# powerSupply.net
KiCad netlist of a schematic drawn in EAGLE
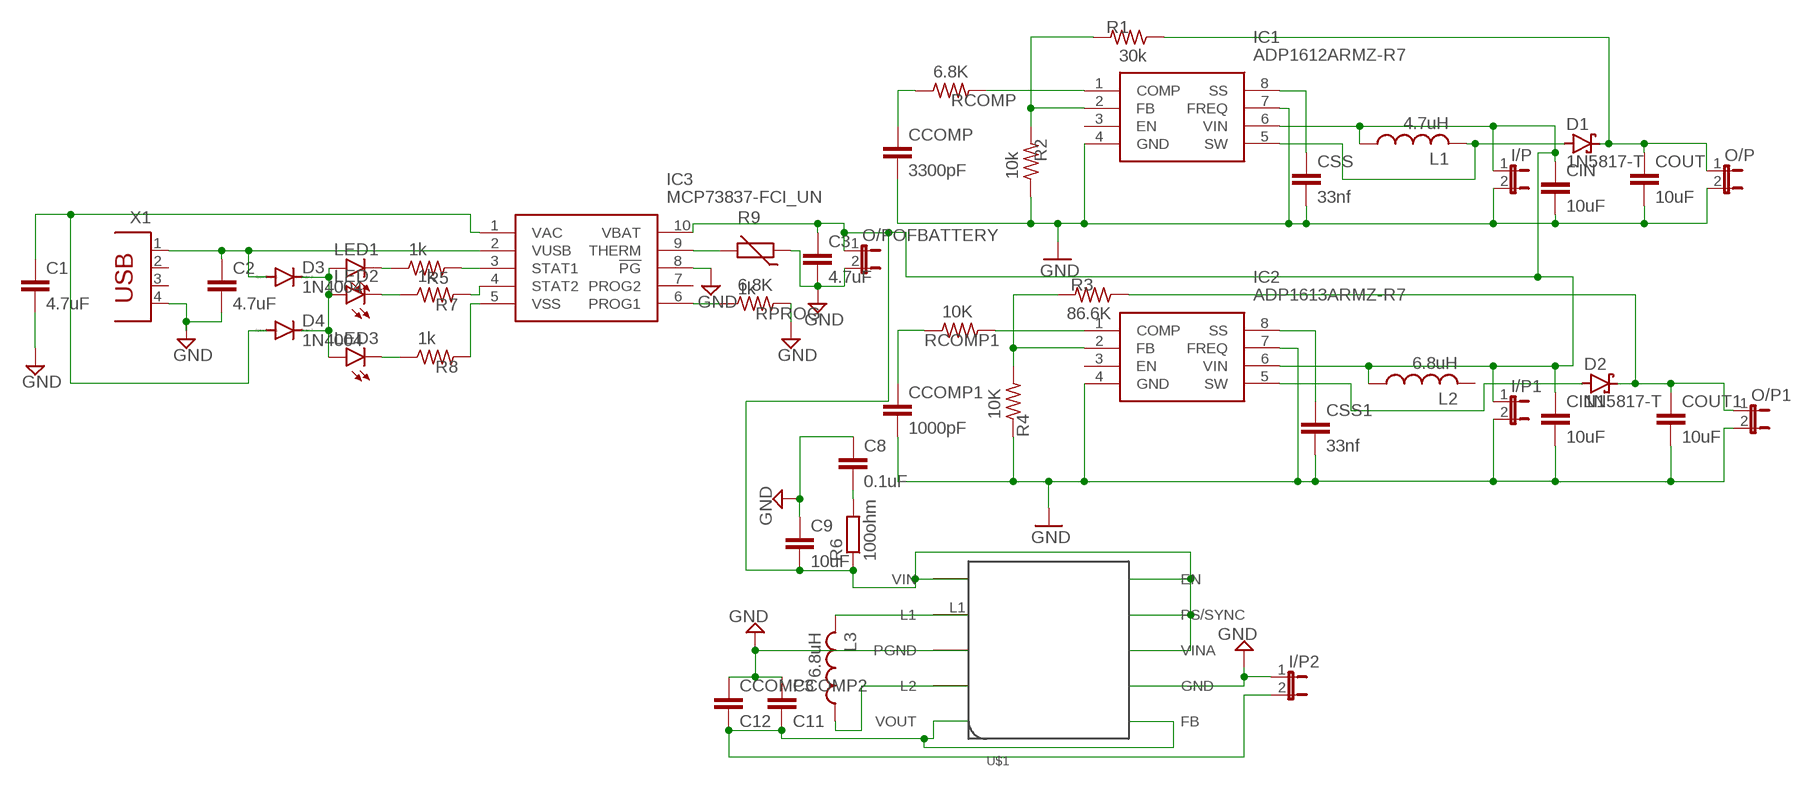
[diagram p0: schematic, sheet 1]

(export (version "E")
  (design (tool "Eeschema 10.0.6"))
  (components
    (comp (ref "C1")
      (value "4.7uF")
      (footprint "eagle-import:C025-024X044")
      (libsource (lib "eagle-import") (part "C-EU025-024X044"))
    )
    (comp (ref "C2")
      (value "4.7uF")
      (footprint "eagle-import:C025-024X044")
      (libsource (lib "eagle-import") (part "C-EU025-024X044"))
    )
    (comp (ref "C3")
      (value "4.7uF")
      (footprint "eagle-import:C025-024X044")
      (libsource (lib "eagle-import") (part "C-EU025-024X044"))
    )
    (comp (ref "C8")
      (value "0.1uF")
      (footprint "eagle-import:C025-024X044")
      (libsource (lib "eagle-import") (part "C-EU025-024X044"))
    )
    (comp (ref "C9")
      (value "10uF")
      (footprint "eagle-import:C025-024X044")
      (libsource (lib "eagle-import") (part "C-EU025-024X044"))
    )
    (comp (ref "CCOMP")
      (value "3300pF")
      (footprint "eagle-import:C025-024X044")
      (libsource (lib "eagle-import") (part "C-EU025-024X044"))
    )
    (comp (ref "CCOMP1")
      (value "1000pF")
      (footprint "eagle-import:C025-024X044")
      (libsource (lib "eagle-import") (part "C-EU025-024X044"))
    )
    (comp (ref "CCOMP2")
      (value "C11")
      (footprint "eagle-import:C025-024X044")
      (libsource (lib "eagle-import") (part "C-EU025-024X044"))
    )
    (comp (ref "CCOMP3")
      (value "C12")
      (footprint "eagle-import:C025-024X044")
      (libsource (lib "eagle-import") (part "C-EU025-024X044"))
    )
    (comp (ref "CIN")
      (value "10uF")
      (footprint "eagle-import:C025-024X044")
      (libsource (lib "eagle-import") (part "C-EU025-024X044"))
    )
    (comp (ref "CIN1")
      (value "10uF")
      (footprint "eagle-import:C025-024X044")
      (libsource (lib "eagle-import") (part "C-EU025-024X044"))
    )
    (comp (ref "COUT")
      (value "10uF")
      (footprint "eagle-import:C025-024X044")
      (libsource (lib "eagle-import") (part "C-EU025-024X044"))
    )
    (comp (ref "COUT1")
      (value "10uF")
      (footprint "eagle-import:C025-024X044")
      (libsource (lib "eagle-import") (part "C-EU025-024X044"))
    )
    (comp (ref "CSS")
      (value "33nf")
      (footprint "eagle-import:C025-024X044")
      (libsource (lib "eagle-import") (part "C-EU025-024X044"))
    )
    (comp (ref "CSS1")
      (value "33nf")
      (footprint "eagle-import:C025-024X044")
      (libsource (lib "eagle-import") (part "C-EU025-024X044"))
    )
    (comp (ref "D1")
      (value "1N5817-T")
      (footprint "eagle-import:SOD323_ST")
      (libsource (lib "eagle-import") (part "BAT60J"))
    )
    (comp (ref "D2")
      (value "1N5817-T")
      (footprint "eagle-import:SOD323_ST")
      (libsource (lib "eagle-import") (part "BAT60J"))
    )
    (comp (ref "D3")
      (value "1N4004")
      (footprint "eagle-import:DO41-10")
      (libsource (lib "eagle-import") (part "1N4004"))
    )
    (comp (ref "D4")
      (value "1N4004")
      (footprint "eagle-import:DO41-10")
      (libsource (lib "eagle-import") (part "1N4004"))
    )
    (comp (ref "I/P")
      (value "JP1E")
      (footprint "eagle-import:JP1")
      (libsource (lib "eagle-import") (part "JP1E"))
    )
    (comp (ref "I/P1")
      (value "JP1E")
      (footprint "eagle-import:JP1")
      (libsource (lib "eagle-import") (part "JP1E"))
    )
    (comp (ref "I/P2")
      (value "JP1E")
      (footprint "eagle-import:JP1")
      (libsource (lib "eagle-import") (part "JP1E"))
    )
    (comp (ref "IC1")
      (value "ADP1612ARMZ-R7")
      (footprint "eagle-import:SOP65P490X110-8N")
      (fields (field (name "MOUSER_PART_NUMBER") "584-ADP1612ARMZ-R7"))
      (libsource (lib "eagle-import") (part "ADP1612ARMZ-R7"))
    )
    (comp (ref "IC2")
      (value "ADP1613ARMZ-R7")
      (footprint "eagle-import:SOP65P490X110-8N")
      (fields (field (name "MOUSER_PART_NUMBER") "584-ADP1613ARMZ-R7"))
      (libsource (lib "eagle-import") (part "ADP1613ARMZ-R7"))
    )
    (comp (ref "IC3")
      (value "MCP73837-FCI_UN")
      (footprint "eagle-import:SOP50P490X110-10N")
      (fields
        (field (name "ARROW_PART_NUMBER") "MCP73837-FCI/UN")
        (field (name "MOUSER_PART_NUMBER") "579-MCP73837-FCI/UN")
      )
      (libsource (lib "eagle-import") (part "MCP73837-FCI_UN"))
    )
    (comp (ref "L1")
      (value "4.7uH")
      (footprint "eagle-import:0204_7")
      (libsource (lib "eagle-import") (part "L-US0204/7"))
    )
    (comp (ref "L2")
      (value "6.8uH")
      (footprint "eagle-import:0204_7")
      (libsource (lib "eagle-import") (part "L-US0204/7"))
    )
    (comp (ref "L3")
      (value "6.8uH")
      (footprint "eagle-import:0204_7")
      (libsource (lib "eagle-import") (part "L-US0204/7"))
    )
    (comp (ref "LED1")
      (value "LED5MM")
      (footprint "eagle-import:LED5MM")
      (libsource (lib "eagle-import") (part "LED5MM"))
    )
    (comp (ref "LED2")
      (value "LED5MM")
      (footprint "eagle-import:LED5MM")
      (libsource (lib "eagle-import") (part "LED5MM"))
    )
    (comp (ref "LED3")
      (value "LED5MM")
      (footprint "eagle-import:LED5MM")
      (libsource (lib "eagle-import") (part "LED5MM"))
    )
    (comp (ref "O/P")
      (value "JP1E")
      (footprint "eagle-import:JP1")
      (libsource (lib "eagle-import") (part "JP1E"))
    )
    (comp (ref "O/P1")
      (value "JP1E")
      (footprint "eagle-import:JP1")
      (libsource (lib "eagle-import") (part "JP1E"))
    )
    (comp (ref "O/POFBATTERY")
      (value "JP1E")
      (footprint "eagle-import:JP1")
      (libsource (lib "eagle-import") (part "JP1E"))
    )
    (comp (ref "R1")
      (value "30k")
      (footprint "eagle-import:0204V")
      (libsource (lib "eagle-import") (part "R-US_0204/2V"))
    )
    (comp (ref "R2")
      (value "10k")
      (footprint "eagle-import:0204V")
      (libsource (lib "eagle-import") (part "R-US_0204/2V"))
    )
    (comp (ref "R3")
      (value "86.6K")
      (footprint "eagle-import:0204V")
      (libsource (lib "eagle-import") (part "R-US_0204/2V"))
    )
    (comp (ref "R4")
      (value "10K")
      (footprint "eagle-import:0204V")
      (libsource (lib "eagle-import") (part "R-US_0204/2V"))
    )
    (comp (ref "R5")
      (value "1k")
      (footprint "eagle-import:0204V")
      (libsource (lib "eagle-import") (part "R-US_0204/2V"))
    )
    (comp (ref "R6")
      (value "100ohm")
      (footprint "eagle-import:0207_10")
      (libsource (lib "eagle-import") (part "R-EU_0207/10"))
    )
    (comp (ref "R7")
      (value "1k")
      (footprint "eagle-import:0204V")
      (libsource (lib "eagle-import") (part "R-US_0204/2V"))
    )
    (comp (ref "R8")
      (value "1k")
      (footprint "eagle-import:0204V")
      (libsource (lib "eagle-import") (part "R-US_0204/2V"))
    )
    (comp (ref "R9")
      (value "1k")
      (footprint "eagle-import:RS-2,5")
      (libsource (lib "eagle-import") (part "THERMISTOR-2,5"))
    )
    (comp (ref "RCOMP")
      (value "6.8K")
      (footprint "eagle-import:0204V")
      (libsource (lib "eagle-import") (part "R-US_0204/2V"))
    )
    (comp (ref "RCOMP1")
      (value "10K")
      (footprint "eagle-import:0204V")
      (libsource (lib "eagle-import") (part "R-US_0204/2V"))
    )
    (comp (ref "RPROG")
      (value "6.8K")
      (footprint "eagle-import:0204V")
      (libsource (lib "eagle-import") (part "R-US_0204/2V"))
    )
    (comp (ref "U$1")
      (value "TPS63002")
      (footprint "eagle-import:TPS63002")
      (libsource (lib "eagle-import") (part "TPS63002"))
    )
    (comp (ref "X1")
      (value "PN87520")
      (footprint "eagle-import:PN87520")
      (libsource (lib "eagle-import") (part "PN87520"))
    )
  )
  (nets
    (net (code "1") (name "GND") (class "Default")
      (node (ref "C1") (pin "2") (pinfunction "2_2") (pintype "passive"))
      (node (ref "C2") (pin "2") (pinfunction "2_2") (pintype "passive"))
      (node (ref "C3") (pin "2") (pinfunction "2_2") (pintype "passive"))
      (node (ref "C8") (pin "1") (pinfunction "1_1") (pintype "passive"))
      (node (ref "C9") (pin "1") (pinfunction "1_1") (pintype "passive"))
      (node (ref "CCOMP") (pin "2") (pinfunction "2_2") (pintype "passive"))
      (node (ref "CCOMP1") (pin "2") (pinfunction "2_2") (pintype "passive"))
      (node (ref "CCOMP2") (pin "1") (pinfunction "1_1") (pintype "passive"))
      (node (ref "CCOMP3") (pin "1") (pinfunction "1_1") (pintype "passive"))
      (node (ref "CIN") (pin "2") (pinfunction "2_2") (pintype "passive"))
      (node (ref "CIN1") (pin "2") (pinfunction "2_2") (pintype "passive"))
      (node (ref "COUT") (pin "2") (pinfunction "2_2") (pintype "passive"))
      (node (ref "COUT1") (pin "2") (pinfunction "2_2") (pintype "passive"))
      (node (ref "CSS") (pin "2") (pinfunction "2_2") (pintype "passive"))
      (node (ref "CSS1") (pin "2") (pinfunction "2_2") (pintype "passive"))
      (node (ref "I/P") (pin "2") (pinfunction "2_2") (pintype "passive"))
      (node (ref "I/P1") (pin "2") (pinfunction "2_2") (pintype "passive"))
      (node (ref "I/P2") (pin "1") (pinfunction "1_1") (pintype "passive"))
      (node (ref "IC1") (pin "4") (pinfunction "GND_4") (pintype "bidirectional"))
      (node (ref "IC1") (pin "7") (pinfunction "FREQ_7") (pintype "bidirectional"))
      (node (ref "IC2") (pin "4") (pinfunction "GND_4") (pintype "bidirectional"))
      (node (ref "IC2") (pin "7") (pinfunction "FREQ_7") (pintype "bidirectional"))
      (node (ref "IC3") (pin "8") (pinfunction "~{PG}_8") (pintype "bidirectional"))
      (node (ref "O/P") (pin "2") (pinfunction "2_2") (pintype "passive"))
      (node (ref "O/P1") (pin "2") (pinfunction "2_2") (pintype "passive"))
      (node (ref "O/POFBATTERY") (pin "2") (pinfunction "2_2") (pintype "passive"))
      (node (ref "R2") (pin "1") (pinfunction "1_1") (pintype "passive"))
      (node (ref "R4") (pin "1") (pinfunction "1_1") (pintype "passive"))
      (node (ref "R9") (pin "1") (pinfunction "1_1") (pintype "passive"))
      (node (ref "RPROG") (pin "2") (pinfunction "2_2") (pintype "passive"))
      (node (ref "U$1") (pin "GND") (pinfunction "GND_GND") (pintype "bidirectional"))
      (node (ref "U$1") (pin "PGND") (pinfunction "PGND_PGND") (pintype "bidirectional"))
      (node (ref "X1") (pin "4") (pinfunction "4_4") (pintype "passive"))
    )
    (net (code "2") (name "Net-(C8-Pad2)") (class "Default")
      (node (ref "C8") (pin "2") (pinfunction "2_2") (pintype "passive"))
      (node (ref "R6") (pin "2") (pinfunction "2_2") (pintype "passive"))
    )
    (net (code "3") (name "Net-(CCOMP-Pad1)") (class "Default")
      (node (ref "CCOMP") (pin "1") (pinfunction "1_1") (pintype "passive"))
      (node (ref "RCOMP") (pin "1") (pinfunction "1_1") (pintype "passive"))
    )
    (net (code "4") (name "Net-(CCOMP1-Pad1)") (class "Default")
      (node (ref "CCOMP1") (pin "1") (pinfunction "1_1") (pintype "passive"))
      (node (ref "RCOMP1") (pin "1") (pinfunction "1_1") (pintype "passive"))
    )
    (net (code "5") (name "Net-(CCOMP2-Pad2)") (class "Default")
      (node (ref "CCOMP2") (pin "2") (pinfunction "2_2") (pintype "passive"))
      (node (ref "CCOMP3") (pin "2") (pinfunction "2_2") (pintype "passive"))
      (node (ref "I/P2") (pin "2") (pinfunction "2_2") (pintype "passive"))
      (node (ref "U$1") (pin "FB") (pinfunction "FB_FB") (pintype "bidirectional"))
      (node (ref "U$1") (pin "VOUT") (pinfunction "VOUT_VOUT") (pintype "bidirectional"))
    )
    (net (code "6") (name "Net-(COUT-Pad1)") (class "Default")
      (node (ref "COUT") (pin "1") (pinfunction "1_1") (pintype "passive"))
      (node (ref "D1") (pin "C") (pinfunction "C_C") (pintype "passive"))
      (node (ref "O/P") (pin "1") (pinfunction "1_1") (pintype "passive"))
      (node (ref "R1") (pin "1") (pinfunction "1_1") (pintype "passive"))
    )
    (net (code "7") (name "Net-(COUT1-Pad1)") (class "Default")
      (node (ref "COUT1") (pin "1") (pinfunction "1_1") (pintype "passive"))
      (node (ref "D2") (pin "C") (pinfunction "C_C") (pintype "passive"))
      (node (ref "O/P1") (pin "1") (pinfunction "1_1") (pintype "passive"))
      (node (ref "R3") (pin "1") (pinfunction "1_1") (pintype "passive"))
    )
    (net (code "8") (name "Net-(D3-PadC)") (class "Default")
      (node (ref "D3") (pin "C") (pinfunction "C_C") (pintype "passive"))
      (node (ref "D4") (pin "C") (pinfunction "C_C") (pintype "passive"))
      (node (ref "LED1") (pin "A") (pinfunction "A_A") (pintype "passive"))
      (node (ref "LED2") (pin "A") (pinfunction "A_A") (pintype "passive"))
      (node (ref "LED3") (pin "A") (pinfunction "A_A") (pintype "passive"))
    )
    (net (code "9") (name "Net-(IC1-COMP)") (class "Default")
      (node (ref "IC1") (pin "1") (pinfunction "COMP_1") (pintype "bidirectional"))
      (node (ref "RCOMP") (pin "2") (pinfunction "2_2") (pintype "passive"))
    )
    (net (code "10") (name "Net-(IC1-FB)") (class "Default")
      (node (ref "IC1") (pin "2") (pinfunction "FB_2") (pintype "bidirectional"))
      (node (ref "R1") (pin "2") (pinfunction "2_2") (pintype "passive"))
      (node (ref "R2") (pin "2") (pinfunction "2_2") (pintype "passive"))
    )
    (net (code "11") (name "Net-(IC1-SS)") (class "Default")
      (node (ref "CSS") (pin "1") (pinfunction "1_1") (pintype "passive"))
      (node (ref "IC1") (pin "8") (pinfunction "SS_8") (pintype "bidirectional"))
    )
    (net (code "12") (name "Net-(IC1-SW)") (class "Default")
      (node (ref "D1") (pin "A") (pinfunction "A_A") (pintype "passive"))
      (node (ref "IC1") (pin "5") (pinfunction "SW_5") (pintype "bidirectional"))
      (node (ref "L1") (pin "2") (pinfunction "2_2") (pintype "passive"))
    )
    (net (code "13") (name "Net-(IC1-VIN)") (class "Default")
      (node (ref "C3") (pin "1") (pinfunction "1_1") (pintype "passive"))
      (node (ref "C9") (pin "2") (pinfunction "2_2") (pintype "passive"))
      (node (ref "CIN") (pin "1") (pinfunction "1_1") (pintype "passive"))
      (node (ref "CIN1") (pin "1") (pinfunction "1_1") (pintype "passive"))
      (node (ref "I/P") (pin "1") (pinfunction "1_1") (pintype "passive"))
      (node (ref "I/P1") (pin "1") (pinfunction "1_1") (pintype "passive"))
      (node (ref "IC1") (pin "6") (pinfunction "VIN_6") (pintype "bidirectional"))
      (node (ref "IC2") (pin "6") (pinfunction "VIN_6") (pintype "bidirectional"))
      (node (ref "IC3") (pin "10") (pinfunction "VBAT_10") (pintype "bidirectional"))
      (node (ref "L1") (pin "1") (pinfunction "1_1") (pintype "passive"))
      (node (ref "L2") (pin "1") (pinfunction "1_1") (pintype "passive"))
      (node (ref "O/POFBATTERY") (pin "1") (pinfunction "1_1") (pintype "passive"))
      (node (ref "R6") (pin "1") (pinfunction "1_1") (pintype "passive"))
      (node (ref "U$1") (pin "EN") (pinfunction "EN_EN") (pintype "bidirectional"))
      (node (ref "U$1") (pin "PS/SYNC") (pinfunction "PS/SYNC_PS/SYNC") (pintype "bidirectional"))
      (node (ref "U$1") (pin "VIN") (pinfunction "VIN_VIN") (pintype "bidirectional"))
      (node (ref "U$1") (pin "VINA") (pinfunction "VINA_VINA") (pintype "bidirectional"))
    )
    (net (code "14") (name "Net-(IC2-COMP)") (class "Default")
      (node (ref "IC2") (pin "1") (pinfunction "COMP_1") (pintype "bidirectional"))
      (node (ref "RCOMP1") (pin "2") (pinfunction "2_2") (pintype "passive"))
    )
    (net (code "15") (name "Net-(IC2-FB)") (class "Default")
      (node (ref "IC2") (pin "2") (pinfunction "FB_2") (pintype "bidirectional"))
      (node (ref "R3") (pin "2") (pinfunction "2_2") (pintype "passive"))
      (node (ref "R4") (pin "2") (pinfunction "2_2") (pintype "passive"))
    )
    (net (code "16") (name "Net-(IC2-SS)") (class "Default")
      (node (ref "CSS1") (pin "1") (pinfunction "1_1") (pintype "passive"))
      (node (ref "IC2") (pin "8") (pinfunction "SS_8") (pintype "bidirectional"))
    )
    (net (code "17") (name "Net-(IC2-SW)") (class "Default")
      (node (ref "D2") (pin "A") (pinfunction "A_A") (pintype "passive"))
      (node (ref "IC2") (pin "5") (pinfunction "SW_5") (pintype "bidirectional"))
    )
    (net (code "18") (name "Net-(IC3-PROG1)") (class "Default")
      (node (ref "IC3") (pin "6") (pinfunction "PROG1_6") (pintype "bidirectional"))
      (node (ref "RPROG") (pin "1") (pinfunction "1_1") (pintype "passive"))
    )
    (net (code "19") (name "Net-(IC3-STAT1)") (class "Default")
      (node (ref "IC3") (pin "3") (pinfunction "STAT1_3") (pintype "bidirectional"))
      (node (ref "R5") (pin "2") (pinfunction "2_2") (pintype "passive"))
    )
    (net (code "20") (name "Net-(IC3-STAT2)") (class "Default")
      (node (ref "IC3") (pin "4") (pinfunction "STAT2_4") (pintype "bidirectional"))
      (node (ref "R7") (pin "2") (pinfunction "2_2") (pintype "passive"))
    )
    (net (code "21") (name "Net-(IC3-THERM)") (class "Default")
      (node (ref "IC3") (pin "9") (pinfunction "THERM_9") (pintype "bidirectional"))
      (node (ref "R9") (pin "2") (pinfunction "2_2") (pintype "passive"))
    )
    (net (code "22") (name "Net-(IC3-VAC)") (class "Default")
      (node (ref "C1") (pin "1") (pinfunction "1_1") (pintype "passive"))
      (node (ref "D4") (pin "A") (pinfunction "A_A") (pintype "passive"))
      (node (ref "IC3") (pin "1") (pinfunction "VAC_1") (pintype "bidirectional"))
    )
    (net (code "23") (name "Net-(IC3-VSS)") (class "Default")
      (node (ref "IC3") (pin "5") (pinfunction "VSS_5") (pintype "power_in"))
      (node (ref "R8") (pin "2") (pinfunction "2_2") (pintype "passive"))
    )
    (net (code "24") (name "Net-(IC3-VUSB)") (class "Default")
      (node (ref "C2") (pin "1") (pinfunction "1_1") (pintype "passive"))
      (node (ref "D3") (pin "A") (pinfunction "A_A") (pintype "passive"))
      (node (ref "IC3") (pin "2") (pinfunction "VUSB_2") (pintype "bidirectional"))
      (node (ref "X1") (pin "1") (pinfunction "1_1") (pintype "passive"))
    )
    (net (code "25") (name "Net-(L3-Pad1)") (class "Default")
      (node (ref "L3") (pin "1") (pinfunction "1_1") (pintype "passive"))
      (node (ref "U$1") (pin "L2") (pinfunction "L2_L2") (pintype "bidirectional"))
    )
    (net (code "26") (name "Net-(L3-Pad2)") (class "Default")
      (node (ref "L3") (pin "2") (pinfunction "2_2") (pintype "passive"))
      (node (ref "U$1") (pin "L1") (pinfunction "L1_L1") (pintype "bidirectional"))
    )
    (net (code "27") (name "Net-(LED1-C)") (class "Default")
      (node (ref "LED1") (pin "K") (pinfunction "C_K") (pintype "passive"))
      (node (ref "R5") (pin "1") (pinfunction "1_1") (pintype "passive"))
    )
    (net (code "28") (name "Net-(LED2-C)") (class "Default")
      (node (ref "LED2") (pin "K") (pinfunction "C_K") (pintype "passive"))
      (node (ref "R7") (pin "1") (pinfunction "1_1") (pintype "passive"))
    )
    (net (code "29") (name "Net-(LED3-C)") (class "Default")
      (node (ref "LED3") (pin "K") (pinfunction "C_K") (pintype "passive"))
      (node (ref "R8") (pin "1") (pinfunction "1_1") (pintype "passive"))
    )
    (net (code "30") (name "unconnected-(IC1-EN-Pad3)") (class "Default")
      (node (ref "IC1") (pin "3") (pinfunction "EN_3") (pintype "bidirectional"))
    )
    (net (code "31") (name "unconnected-(IC2-EN-Pad3)") (class "Default")
      (node (ref "IC2") (pin "3") (pinfunction "EN_3") (pintype "bidirectional"))
    )
    (net (code "32") (name "unconnected-(IC3-PROG2-Pad7)") (class "Default")
      (node (ref "IC3") (pin "7") (pinfunction "PROG2_7") (pintype "bidirectional"))
    )
    (net (code "33") (name "unconnected-(L2-Pad2)") (class "Default")
      (node (ref "L2") (pin "2") (pinfunction "2_2") (pintype "passive"))
    )
    (net (code "34") (name "unconnected-(X1-Pad2)") (class "Default")
      (node (ref "X1") (pin "2") (pinfunction "2_2") (pintype "passive"))
    )
    (net (code "35") (name "unconnected-(X1-Pad3)") (class "Default")
      (node (ref "X1") (pin "3") (pinfunction "3_3") (pintype "passive"))
    )
  )
)
